# ONA_SensorMoteV1.net
KiCad netlist of a schematic drawn in EAGLE
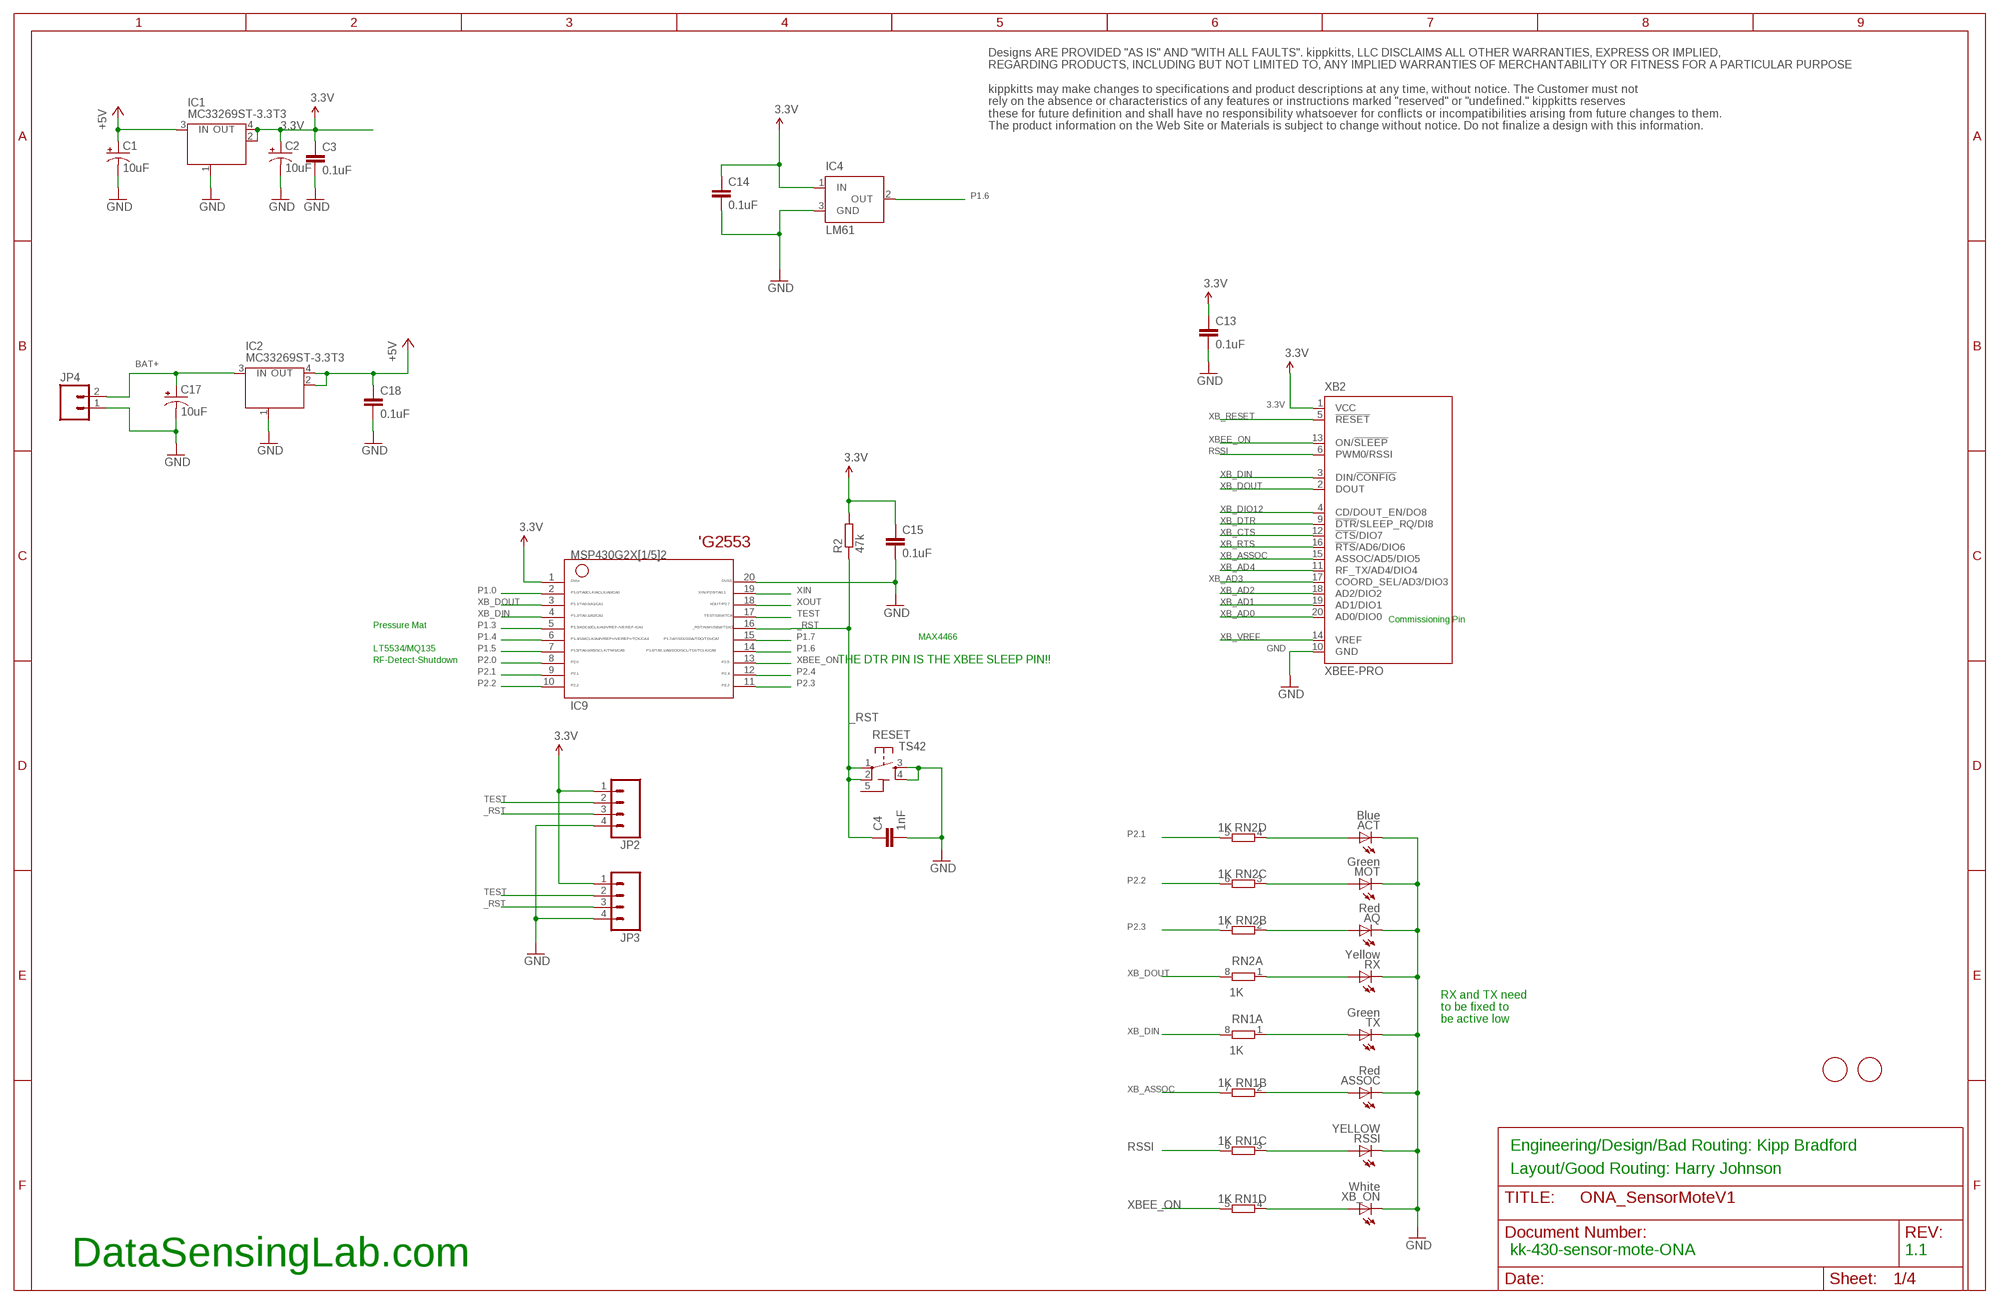
[diagram p0: schematic, sheet 1]
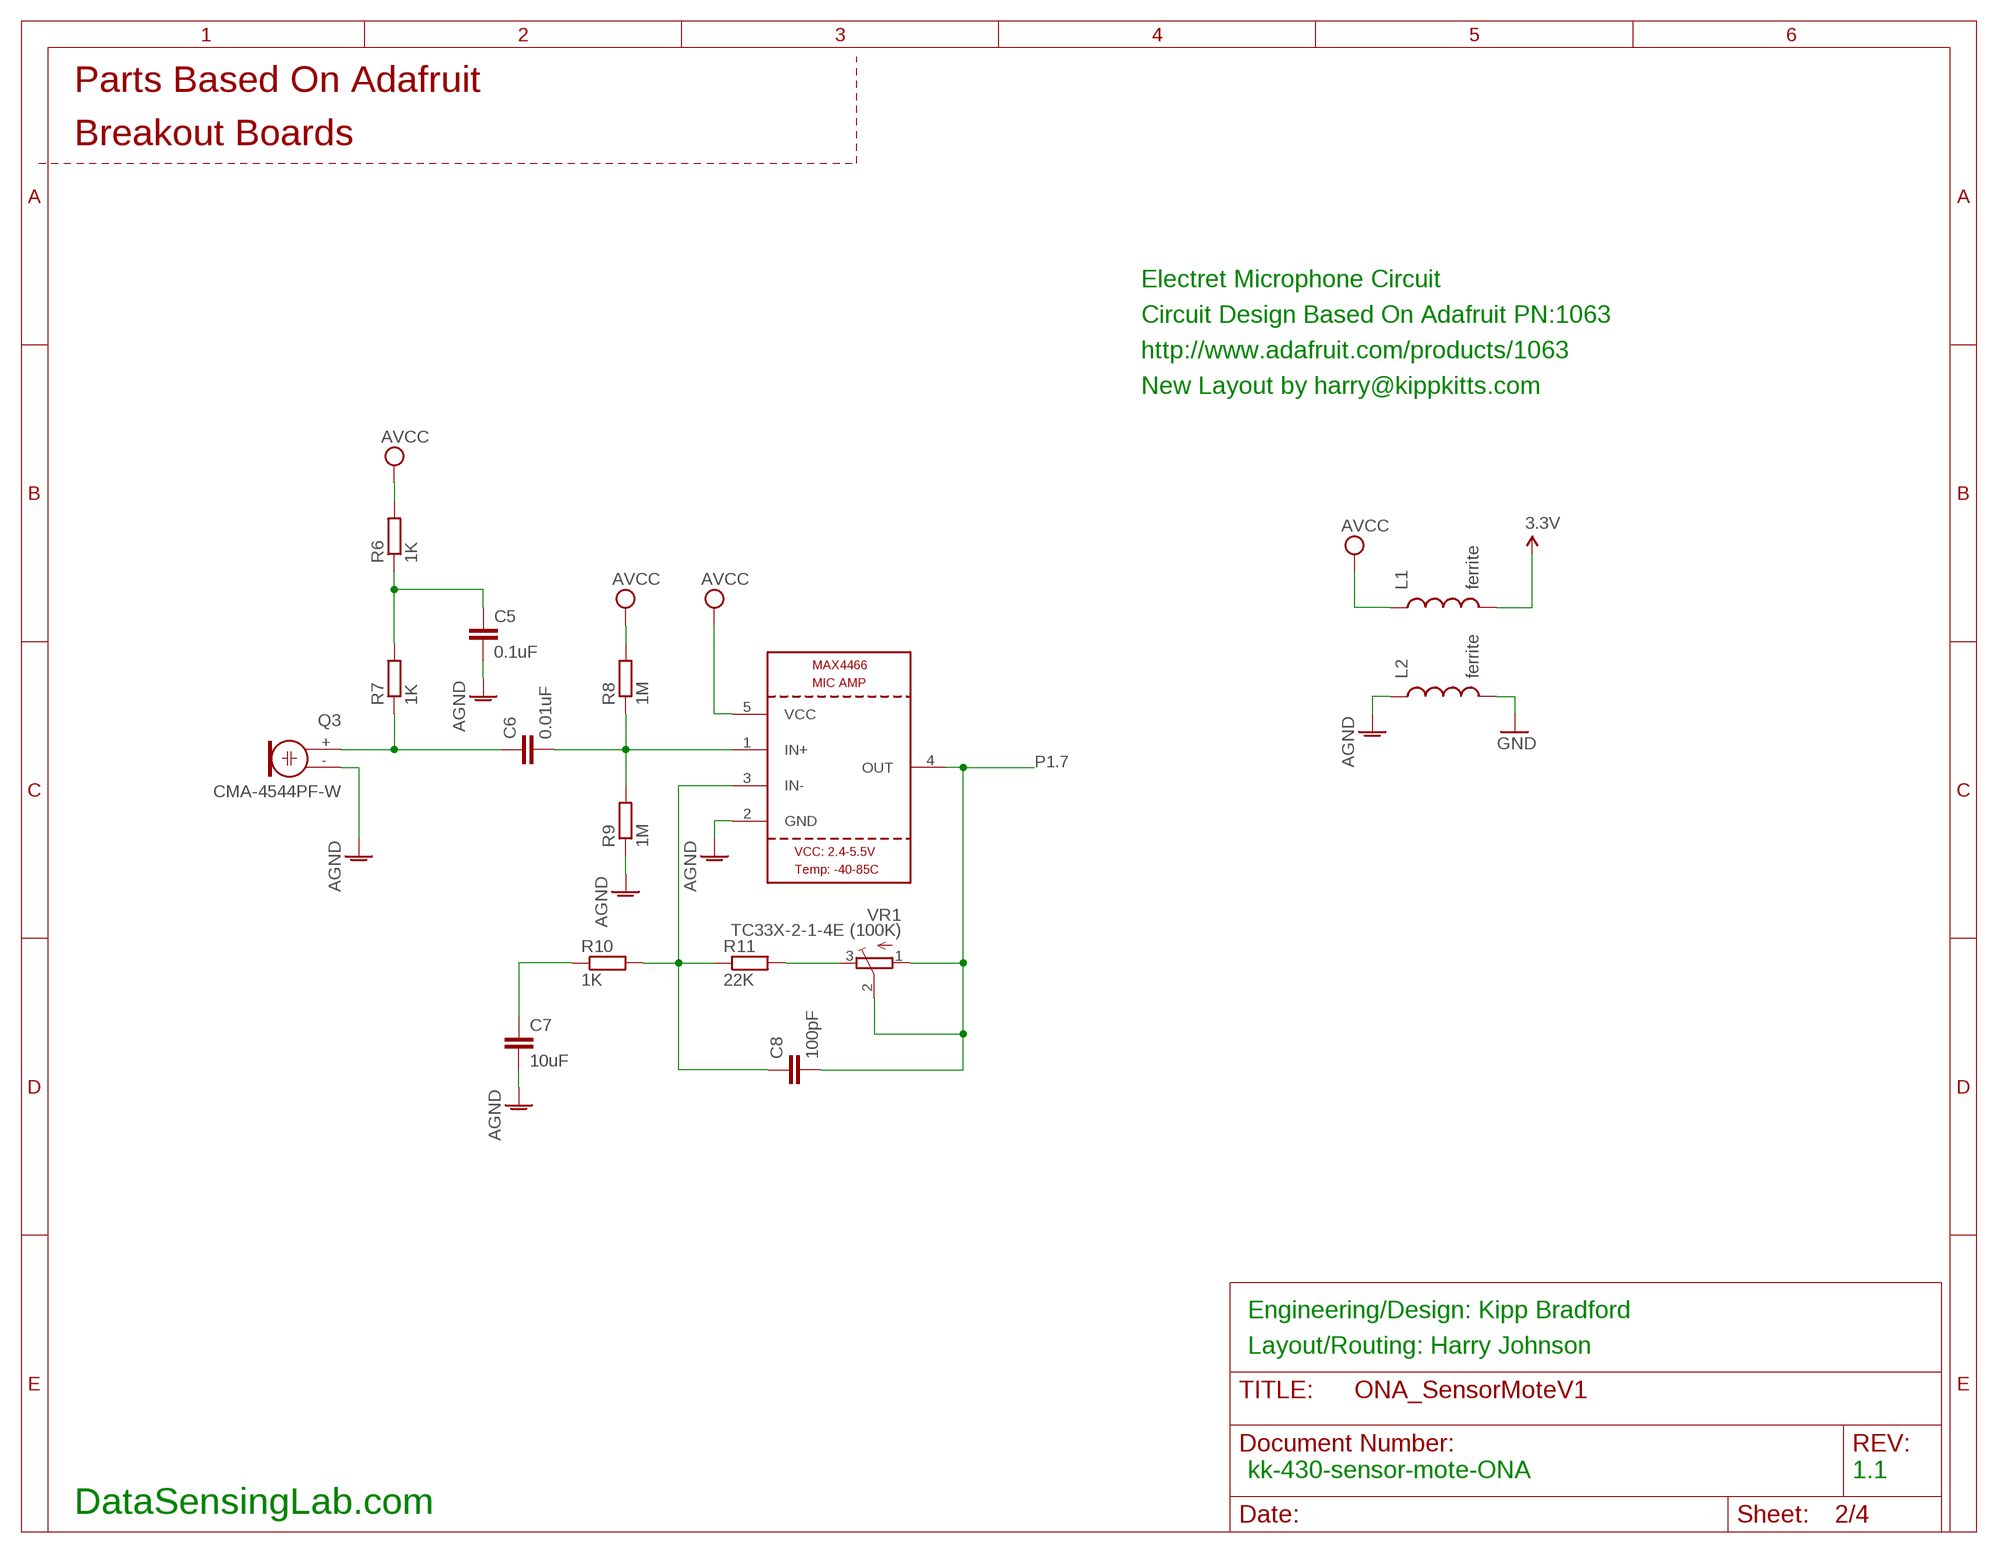
[diagram p1: schematic, sheet 2]
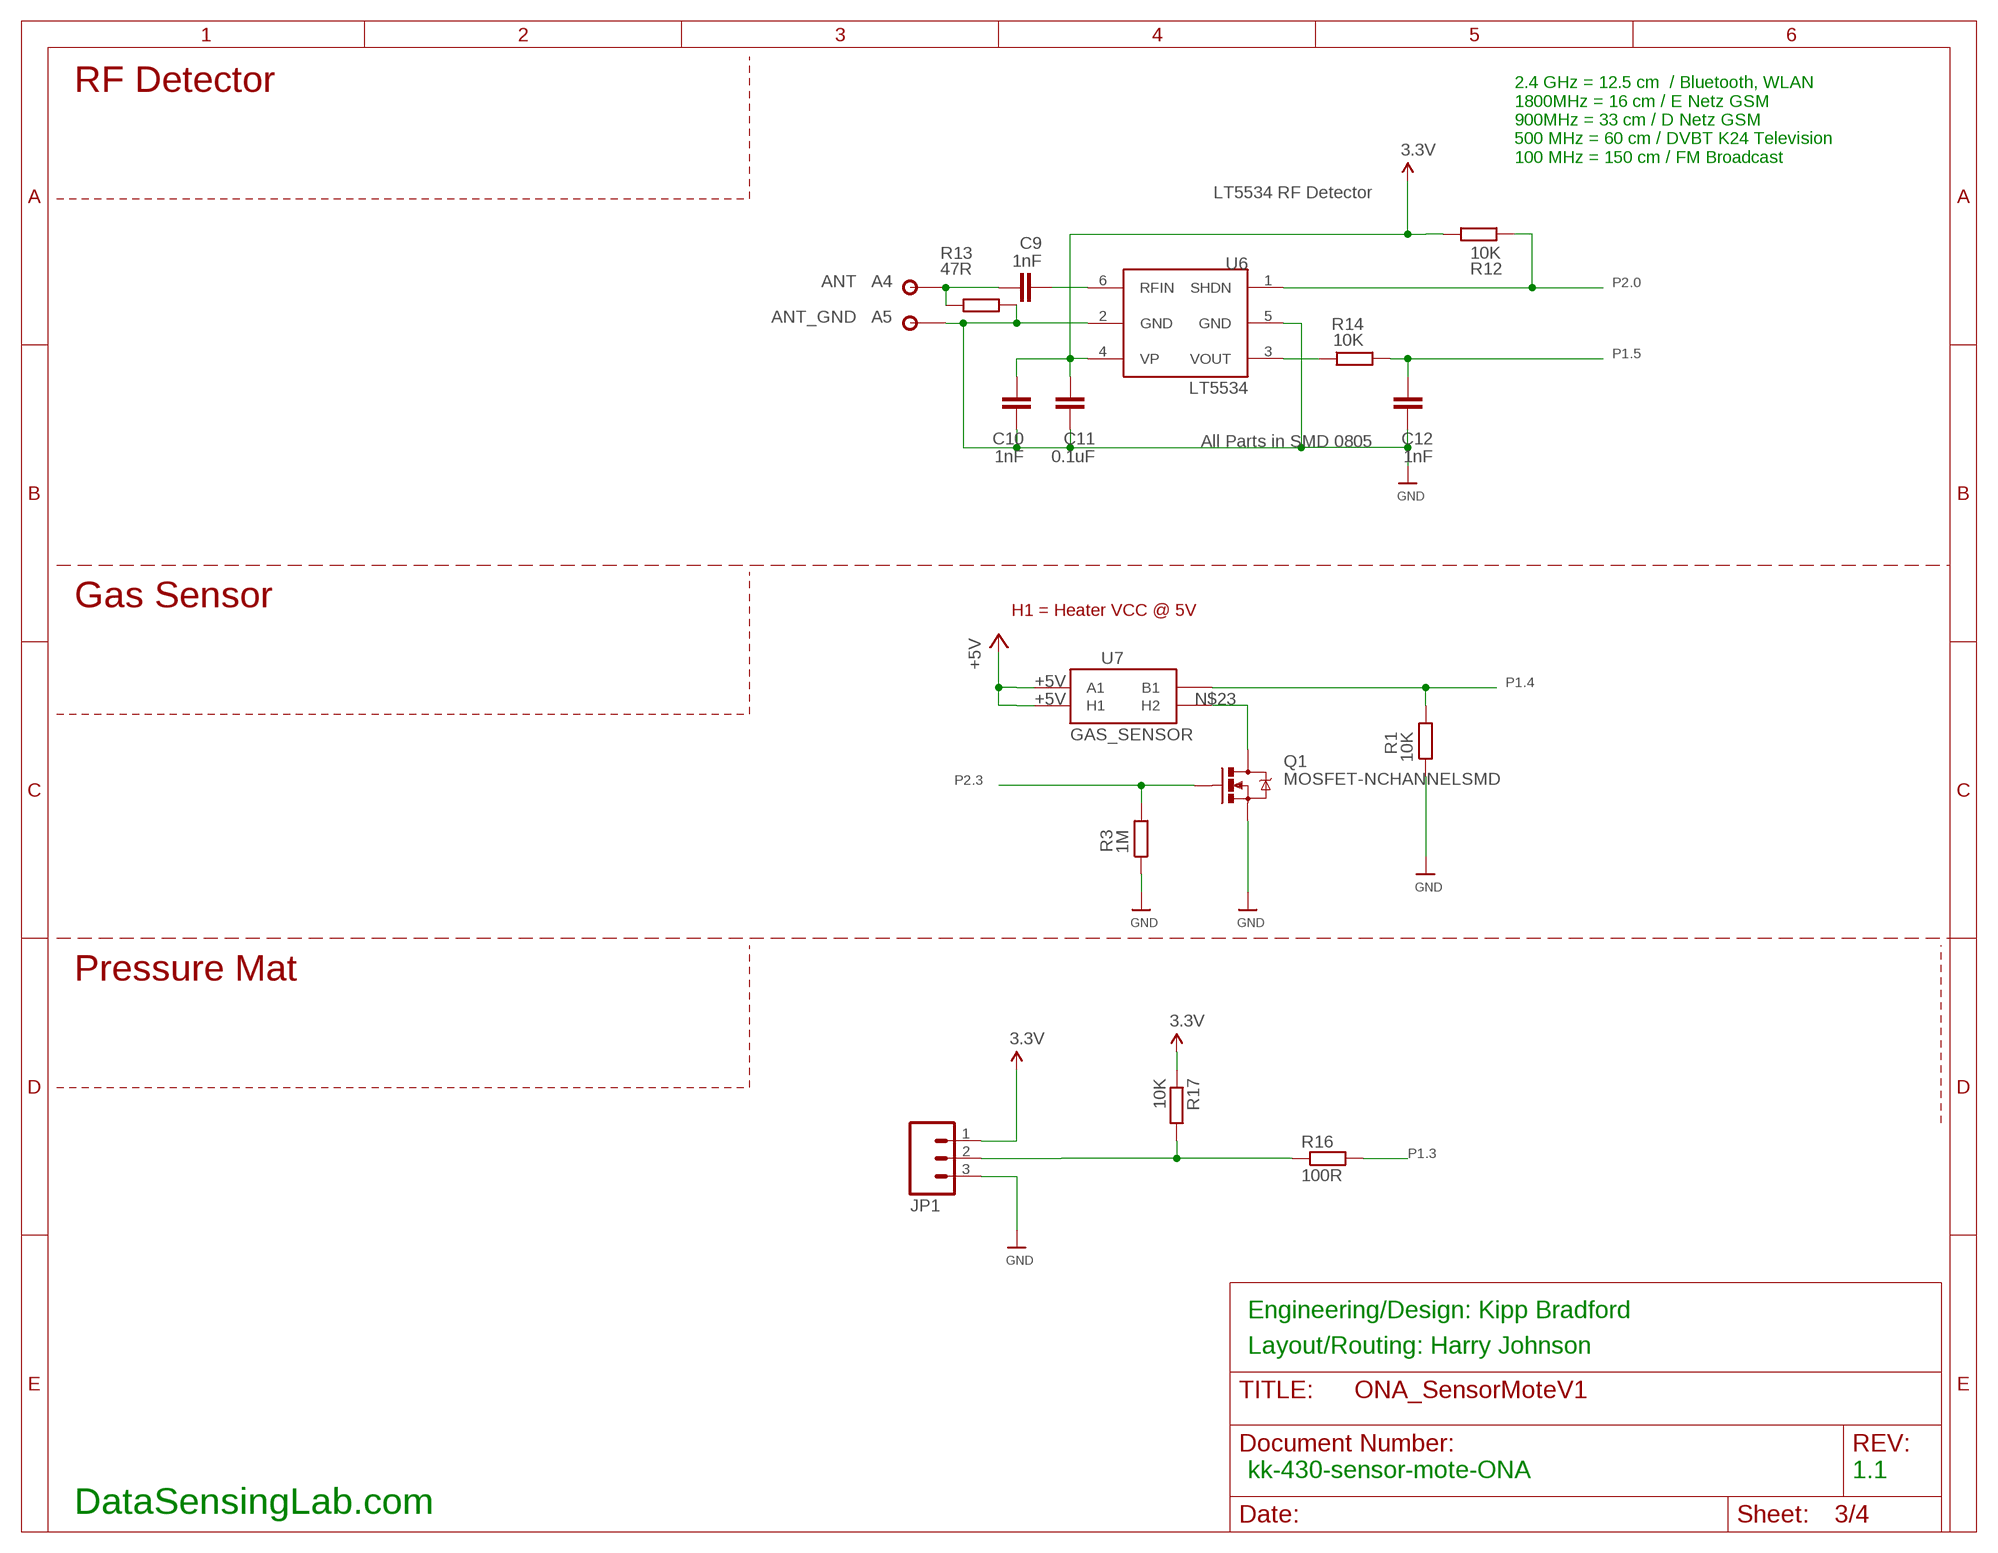
[diagram p2: schematic, sheet 3]
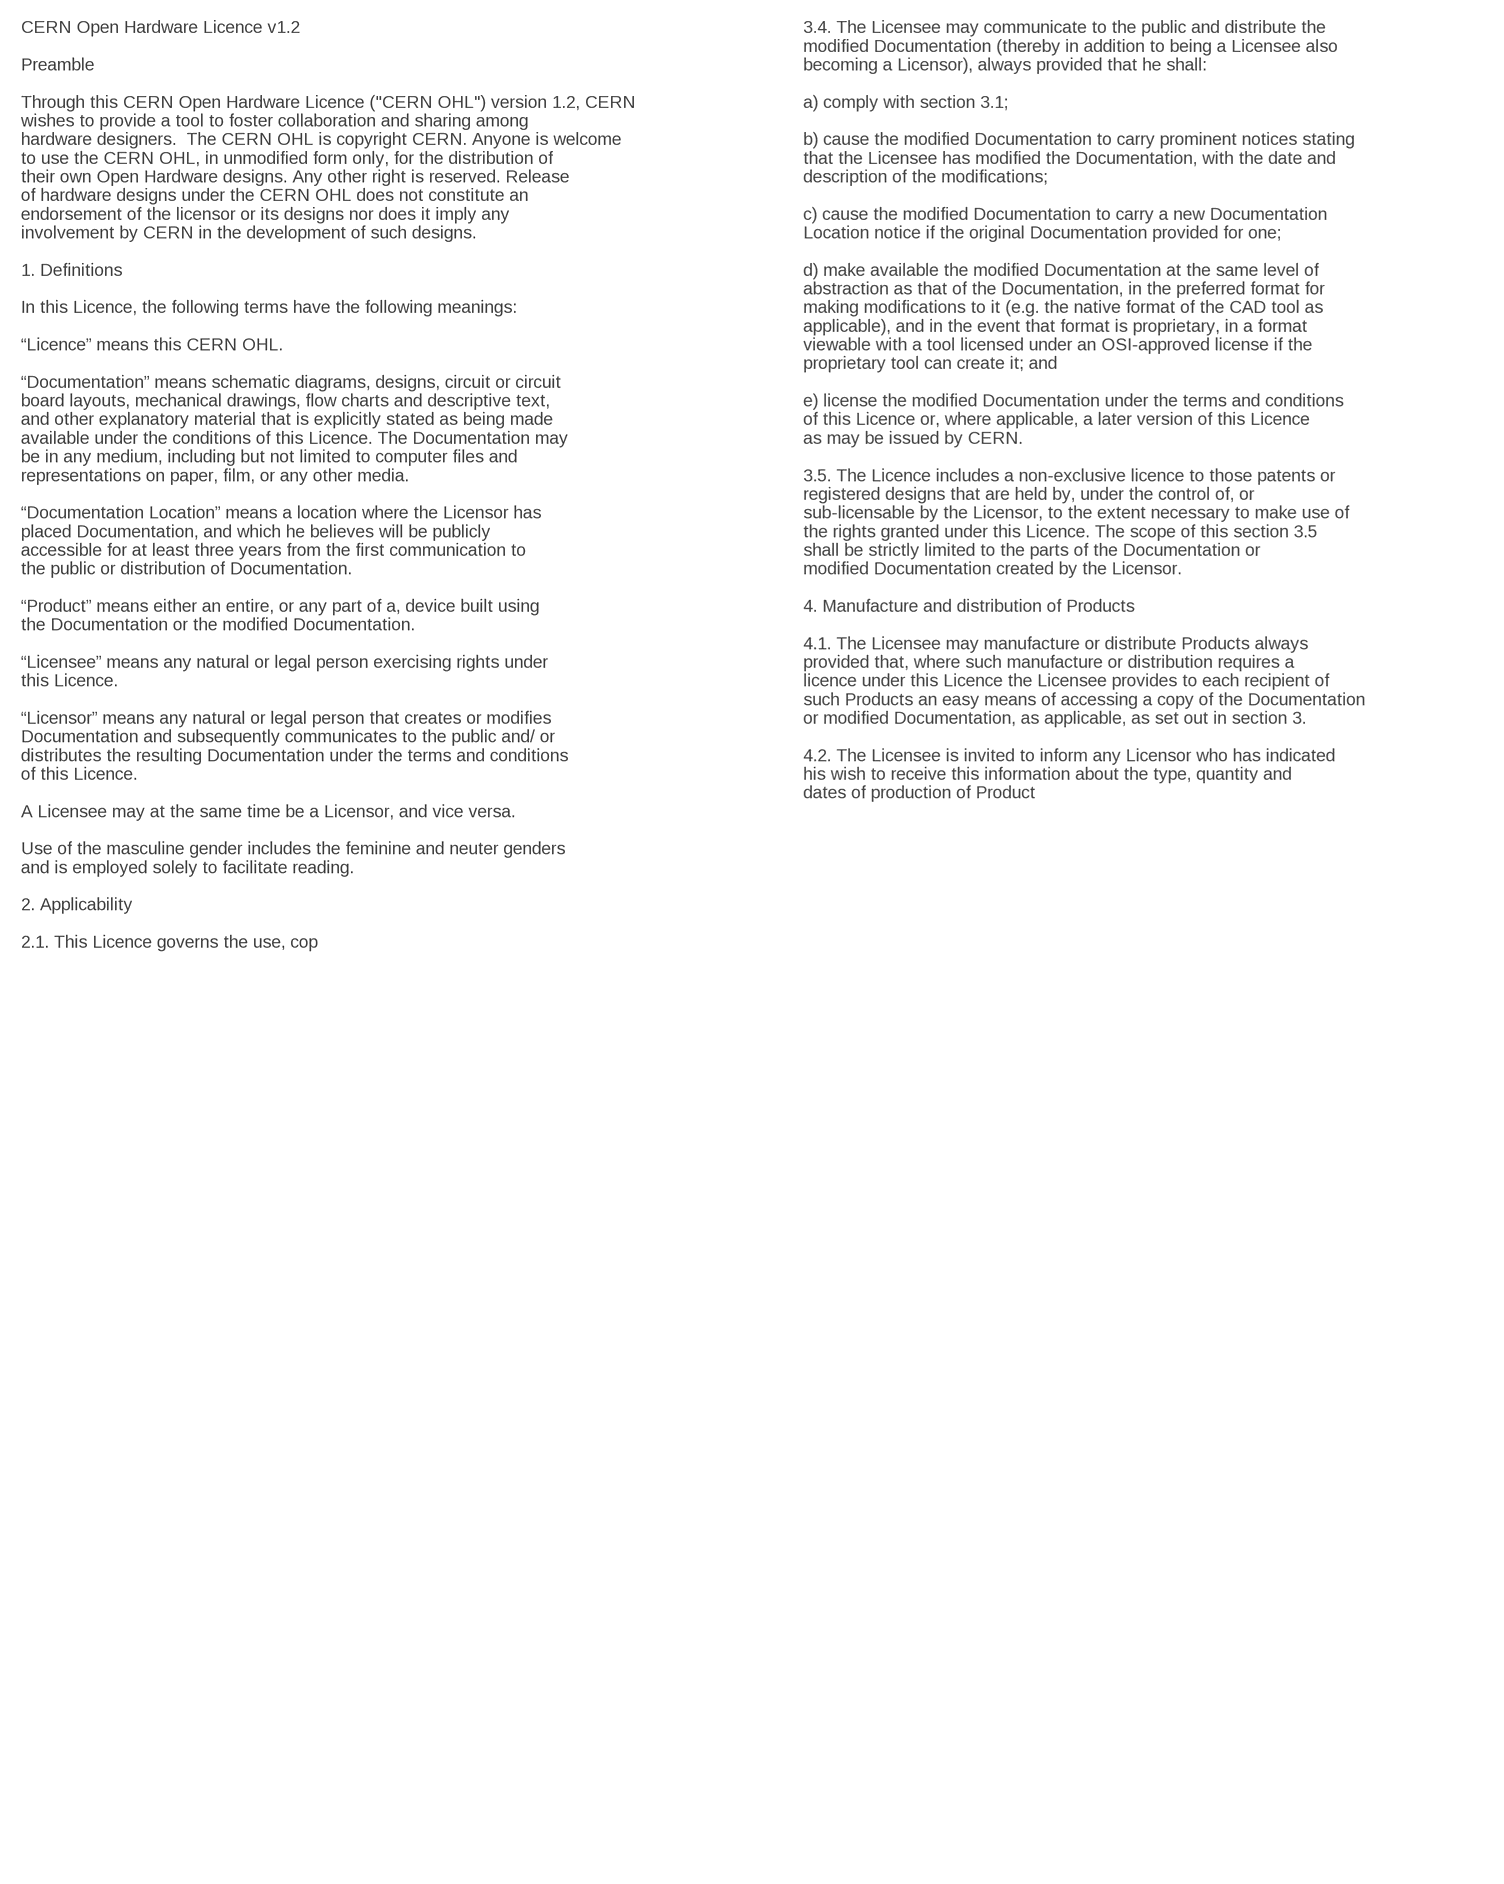
[diagram p3: schematic, sheet 4]

(export (version "E")
  (design (tool "Eeschema 10.0.6"))
  (components
    (comp (ref "A1")
      (value "FIDUCIALMOUNT")
      (footprint "eagle-import:FIDUCIA-MOUNT")
      (libsource (lib "eagle-import") (part "FIDUCIALMOUNT"))
    )
    (comp (ref "A2")
      (value "FIDUCIALMOUNT")
      (footprint "eagle-import:FIDUCIA-MOUNT")
      (libsource (lib "eagle-import") (part "FIDUCIALMOUNT"))
    )
    (comp (ref "ACT")
      (value "Blue")
      (footprint "eagle-import:CHIP-LED0805")
      (libsource (lib "eagle-import") (part "LEDCHIP-LED0805"))
    )
    (comp (ref "AQ")
      (value "Red")
      (footprint "eagle-import:CHIP-LED0805")
      (libsource (lib "eagle-import") (part "LEDCHIP-LED0805"))
    )
    (comp (ref "ASSOC")
      (value "Red")
      (footprint "eagle-import:CHIP-LED0805")
      (libsource (lib "eagle-import") (part "LEDCHIP-LED0805"))
    )
    (comp (ref "C1")
      (value "10uF")
      (footprint "eagle-import:EIA3216")
      (libsource (lib "eagle-import") (part "CAP_POL1206"))
    )
    (comp (ref "C2")
      (value "10uF")
      (footprint "eagle-import:EIA3216")
      (libsource (lib "eagle-import") (part "CAP_POL1206"))
    )
    (comp (ref "C3")
      (value "0.1uF")
      (footprint "eagle-import:C0805K")
      (libsource (lib "eagle-import") (part "C-EUC0805K"))
    )
    (comp (ref "C4")
      (value "1nF")
      (footprint "eagle-import:C0805K")
      (libsource (lib "eagle-import") (part "C-EUC0805K"))
    )
    (comp (ref "C13")
      (value "0.1uF")
      (footprint "eagle-import:C0805K")
      (libsource (lib "eagle-import") (part "C-EUC0805K"))
    )
    (comp (ref "C14")
      (value "0.1uF")
      (footprint "eagle-import:C0805K")
      (libsource (lib "eagle-import") (part "C-EUC0805K"))
    )
    (comp (ref "C15")
      (value "0.1uF")
      (footprint "eagle-import:C0805K")
      (libsource (lib "eagle-import") (part "C-EUC0805K"))
    )
    (comp (ref "C17")
      (value "10uF")
      (footprint "eagle-import:EIA3216")
      (libsource (lib "eagle-import") (part "CAP_POL1206"))
    )
    (comp (ref "C18")
      (value "0.1uF")
      (footprint "eagle-import:C0805K")
      (libsource (lib "eagle-import") (part "C-EUC0805K"))
    )
    (comp (ref "DISCLAIMER1")
      (value "DISCLAIMERV1")
      (footprint "eagle-import:DISCLAIMER")
      (libsource (lib "eagle-import") (part "DISCLAIMERV1"))
    )
    (comp (ref "IC1")
      (value "MC33269ST-3.3T3")
      (footprint "eagle-import:SOT223")
      (libsource (lib "eagle-import") (part "MC33269ST-3.3T3"))
    )
    (comp (ref "IC2")
      (value "MC33269ST-3.3T3")
      (footprint "eagle-import:SOT223")
      (libsource (lib "eagle-import") (part "MC33269ST-3.3T3"))
    )
    (comp (ref "IC4")
      (value "LM61")
      (footprint "eagle-import:SOT23")
      (fields (field (name "MF") "MAXIM") (field (name "MPN") "MAX6520EUR-T"))
      (libsource (lib "eagle-import") (part "MAX6520"))
    )
    (comp (ref "IC9")
      (value "G2X[1/5]2---PW20")
      (footprint "eagle-import:PW20")
      (libsource (lib "eagle-import") (part "G2X[1/5]2---PW20"))
    )
    (comp (ref "JP2")
      (value "M04SMD")
      (footprint "eagle-import:1X04-SMD")
      (libsource (lib "eagle-import") (part "M04SMD"))
    )
    (comp (ref "JP3")
      (value "M04PTH")
      (footprint "eagle-import:1X04")
      (libsource (lib "eagle-import") (part "M04PTH"))
    )
    (comp (ref "JP4")
      (value "M02")
      (footprint "eagle-import:1X02_LONGPADS")
      (libsource (lib "eagle-import") (part "M02"))
    )
    (comp (ref "MOT")
      (value "Green")
      (footprint "eagle-import:CHIP-LED0805")
      (libsource (lib "eagle-import") (part "LEDCHIP-LED0805"))
    )
    (comp (ref "R2")
      (value "47k")
      (footprint "eagle-import:R0805")
      (libsource (lib "eagle-import") (part "resistor_R-EU_R0805"))
    )
    (comp (ref "RESET")
      (value "TS42")
      (footprint "eagle-import:TS42")
      (libsource (lib "eagle-import") (part "TS42"))
    )
    (comp (ref "RN1")
      (value "1K")
      (footprint "eagle-import:CAY16")
      (libsource (lib "eagle-import") (part "4R-NCAY16"))
    )
    (comp (ref "RN2")
      (value "1K")
      (footprint "eagle-import:CAY16")
      (fields (field (name "OC_FARNELL") "unknown") (field (name "OC_NEWARK") "unknown"))
      (libsource (lib "eagle-import") (part "4R-NCAY16"))
    )
    (comp (ref "RSSI")
      (value "YELLOW")
      (footprint "eagle-import:CHIP-LED0805")
      (libsource (lib "eagle-import") (part "LEDCHIP-LED0805"))
    )
    (comp (ref "RX")
      (value "Yellow")
      (footprint "eagle-import:CHIP-LED0805")
      (libsource (lib "eagle-import") (part "LEDCHIP-LED0805"))
    )
    (comp (ref "TX")
      (value "Green")
      (footprint "eagle-import:CHIP-LED0805")
      (libsource (lib "eagle-import") (part "LEDCHIP-LED0805"))
    )
    (comp (ref "XB2")
      (value "XBEE-PRO")
      (footprint "eagle-import:XBEE-PRO")
      (fields (field (name "MPN") "XBP24-AWI-001"))
      (libsource (lib "eagle-import") (part "XBEE-PRO"))
    )
    (comp (ref "XB_ON")
      (value "White")
      (footprint "eagle-import:CHIP-LED0805")
      (libsource (lib "eagle-import") (part "LEDCHIP-LED0805"))
    )
    (comp (ref "C5")
      (value "0.1uF")
      (footprint "eagle-import:C0805K")
      (libsource (lib "eagle-import") (part "C-EUC0805K"))
    )
    (comp (ref "C6")
      (value "0.01uF")
      (footprint "eagle-import:C0805K")
      (libsource (lib "eagle-import") (part "C-EUC0805K"))
    )
    (comp (ref "C7")
      (value "10uF")
      (footprint "eagle-import:C0805K")
      (libsource (lib "eagle-import") (part "C-EUC0805K"))
    )
    (comp (ref "C8")
      (value "100pF")
      (footprint "eagle-import:C0805K")
      (libsource (lib "eagle-import") (part "C-EUC0805K"))
    )
    (comp (ref "L1")
      (value "ferrite")
      (footprint "eagle-import:0603")
      (libsource (lib "eagle-import") (part "INDUCTOR0603"))
    )
    (comp (ref "L2")
      (value "ferrite")
      (footprint "eagle-import:0603")
      (libsource (lib "eagle-import") (part "INDUCTOR0603"))
    )
    (comp (ref "Q3")
      (value "CMA-4544PF-W")
      (footprint "eagle-import:9.7ELECTRET")
      (libsource (lib "eagle-import") (part "ELECTRET"))
    )
    (comp (ref "R6")
      (value "1K")
      (footprint "eagle-import:R0805")
      (libsource (lib "eagle-import") (part "resistor_R-EU_R0805"))
    )
    (comp (ref "R7")
      (value "1K")
      (footprint "eagle-import:R0805")
      (libsource (lib "eagle-import") (part "resistor_R-EU_R0805"))
    )
    (comp (ref "R8")
      (value "1M")
      (footprint "eagle-import:R0805")
      (libsource (lib "eagle-import") (part "resistor_R-EU_R0805"))
    )
    (comp (ref "R9")
      (value "1M")
      (footprint "eagle-import:R0805")
      (libsource (lib "eagle-import") (part "resistor_R-EU_R0805"))
    )
    (comp (ref "R10")
      (value "1K")
      (footprint "eagle-import:R0805")
      (libsource (lib "eagle-import") (part "resistor_R-EU_R0805"))
    )
    (comp (ref "R11")
      (value "22K")
      (footprint "eagle-import:R0805")
      (libsource (lib "eagle-import") (part "resistor_R-EU_R0805"))
    )
    (comp (ref "U5")
      (value "MAX4466SC70")
      (footprint "eagle-import:SC70-5L")
      (libsource (lib "eagle-import") (part "MAX4466SC70"))
    )
    (comp (ref "VR1")
      (value "TC33X-2-1-4E (100K)")
      (footprint "eagle-import:TC33X")
      (libsource (lib "eagle-import") (part "TRIMPOTTC33X"))
    )
    (comp (ref "A4")
      (value "ANT")
      (footprint "eagle-import:PAD146")
      (libsource (lib "eagle-import") (part "PAD1,46MM"))
    )
    (comp (ref "A5")
      (value "ANT_GND")
      (footprint "eagle-import:PAD146")
      (libsource (lib "eagle-import") (part "PAD1,46MM"))
    )
    (comp (ref "C9")
      (value "1nF")
      (footprint "eagle-import:C0805K")
      (libsource (lib "eagle-import") (part "C-EUC0805K"))
    )
    (comp (ref "C10")
      (value "1nF")
      (footprint "eagle-import:C0805K")
      (libsource (lib "eagle-import") (part "C-EUC0805K"))
    )
    (comp (ref "C11")
      (value "0.1uF")
      (footprint "eagle-import:C0805K")
      (libsource (lib "eagle-import") (part "C-EUC0805K"))
    )
    (comp (ref "C12")
      (value "1nF")
      (footprint "eagle-import:C0805K")
      (libsource (lib "eagle-import") (part "C-EUC0805K"))
    )
    (comp (ref "JP1")
      (value "M03LOCK")
      (footprint "eagle-import:1X03_LOCK")
      (libsource (lib "eagle-import") (part "M03LOCK"))
    )
    (comp (ref "Q1")
      (value "MOSFET-NCHANNELSMD")
      (footprint "eagle-import:SOT23-3")
      (libsource (lib "eagle-import") (part "MOSFET-NCHANNELSMD"))
    )
    (comp (ref "R1")
      (value "10K")
      (footprint "eagle-import:R0805")
      (libsource (lib "eagle-import") (part "R-EU_R0805"))
    )
    (comp (ref "R3")
      (value "1M")
      (footprint "eagle-import:R0805")
      (libsource (lib "eagle-import") (part "R-EU_R0805"))
    )
    (comp (ref "R12")
      (value "10K")
      (footprint "eagle-import:R0805")
      (libsource (lib "eagle-import") (part "R-EU_R0805"))
    )
    (comp (ref "R13")
      (value "47R")
      (footprint "eagle-import:R0805")
      (libsource (lib "eagle-import") (part "R-EU_R0805"))
    )
    (comp (ref "R14")
      (value "10K")
      (footprint "eagle-import:R0805")
      (libsource (lib "eagle-import") (part "R-EU_R0805"))
    )
    (comp (ref "R16")
      (value "100R")
      (footprint "eagle-import:R0805")
      (libsource (lib "eagle-import") (part "R-EU_R0805"))
    )
    (comp (ref "R17")
      (value "10K")
      (footprint "eagle-import:R0805")
      (libsource (lib "eagle-import") (part "R-EU_R0805"))
    )
    (comp (ref "U6")
      (value "LT5534")
      (footprint "eagle-import:SC70")
      (libsource (lib "eagle-import") (part "LTC55"))
    )
    (comp (ref "U7")
      (value "GAS_SENSOR")
      (footprint "eagle-import:MQ-3")
      (libsource (lib "eagle-import") (part "GAS_SENSOR"))
    )
  )
  (nets
    (net (code "1") (name "+5V") (class "Default")
      (node (ref "C1") (pin "A") (pinfunction "+_A") (pintype "passive"))
      (node (ref "C18") (pin "1") (pinfunction "1_1") (pintype "passive"))
      (node (ref "IC1") (pin "3") (pinfunction "IN_3") (pintype "input"))
      (node (ref "IC2") (pin "2") (pinfunction "OUT_2") (pintype "passive"))
      (node (ref "IC2") (pin "4") (pinfunction "OUT_4") (pintype "passive"))
      (node (ref "U7") (pin "A1") (pinfunction "A1_A1") (pintype "bidirectional"))
      (node (ref "U7") (pin "HA") (pinfunction "H1_HA") (pintype "bidirectional"))
    )
    (net (code "2") (name "3.3V") (class "Default")
      (node (ref "C10") (pin "2") (pinfunction "2_2") (pintype "passive"))
      (node (ref "C11") (pin "2") (pinfunction "2_2") (pintype "passive"))
      (node (ref "C13") (pin "1") (pinfunction "1_1") (pintype "passive"))
      (node (ref "C14") (pin "1") (pinfunction "1_1") (pintype "passive"))
      (node (ref "C15") (pin "1") (pinfunction "1_1") (pintype "passive"))
      (node (ref "C2") (pin "A") (pinfunction "+_A") (pintype "passive"))
      (node (ref "C3") (pin "1") (pinfunction "1_1") (pintype "passive"))
      (node (ref "IC1") (pin "2") (pinfunction "OUT_2") (pintype "passive"))
      (node (ref "IC1") (pin "4") (pinfunction "OUT_4") (pintype "passive"))
      (node (ref "IC4") (pin "1") (pinfunction "IN_1") (pintype "input"))
      (node (ref "IC9") (pin "1") (pinfunction "1_1") (pintype "bidirectional"))
      (node (ref "JP1") (pin "1") (pinfunction "1_1") (pintype "passive"))
      (node (ref "JP2") (pin "1") (pinfunction "1_1") (pintype "passive"))
      (node (ref "JP3") (pin "1") (pinfunction "1_1") (pintype "passive"))
      (node (ref "L1") (pin "2") (pinfunction "2_2") (pintype "passive"))
      (node (ref "R12") (pin "2") (pinfunction "2_2") (pintype "passive"))
      (node (ref "R17") (pin "1") (pinfunction "1_1") (pintype "passive"))
      (node (ref "R2") (pin "2") (pinfunction "2_2") (pintype "passive"))
      (node (ref "U6") (pin "4") (pinfunction "VP_4") (pintype "bidirectional"))
      (node (ref "XB2") (pin "1") (pinfunction "VCC_1") (pintype "power_in"))
    )
    (net (code "3") (name "5-GND") (class "Default")
      (node (ref "RESET") (pin "5") (pinfunction "5-GND_5") (pintype "power_in"))
    )
    (net (code "4") (name "AGND") (class "Default")
      (node (ref "C5") (pin "2") (pinfunction "2_2") (pintype "passive"))
      (node (ref "C7") (pin "2") (pinfunction "2_2") (pintype "passive"))
      (node (ref "L2") (pin "1") (pinfunction "1_1") (pintype "passive"))
      (node (ref "Q3") (pin "-") (pinfunction "1_-") (pintype "passive"))
      (node (ref "R9") (pin "1") (pinfunction "1_1") (pintype "passive"))
      (node (ref "U5") (pin "2") (pinfunction "GND_2") (pintype "power_in"))
    )
    (net (code "5") (name "BAT+") (class "Default")
      (node (ref "C17") (pin "A") (pinfunction "+_A") (pintype "passive"))
      (node (ref "IC2") (pin "3") (pinfunction "IN_3") (pintype "input"))
      (node (ref "JP4") (pin "2") (pinfunction "2_2") (pintype "passive"))
    )
    (net (code "6") (name "GND") (class "Default")
      (node (ref "A5") (pin "1") (pinfunction "1_1") (pintype "passive"))
      (node (ref "ACT") (pin "C") (pinfunction "C_C") (pintype "passive"))
      (node (ref "AQ") (pin "C") (pinfunction "C_C") (pintype "passive"))
      (node (ref "ASSOC") (pin "C") (pinfunction "C_C") (pintype "passive"))
      (node (ref "C1") (pin "C") (pinfunction "-_C") (pintype "passive"))
      (node (ref "C10") (pin "1") (pinfunction "1_1") (pintype "passive"))
      (node (ref "C11") (pin "1") (pinfunction "1_1") (pintype "passive"))
      (node (ref "C12") (pin "1") (pinfunction "1_1") (pintype "passive"))
      (node (ref "C13") (pin "2") (pinfunction "2_2") (pintype "passive"))
      (node (ref "C14") (pin "2") (pinfunction "2_2") (pintype "passive"))
      (node (ref "C15") (pin "2") (pinfunction "2_2") (pintype "passive"))
      (node (ref "C17") (pin "C") (pinfunction "-_C") (pintype "passive"))
      (node (ref "C18") (pin "2") (pinfunction "2_2") (pintype "passive"))
      (node (ref "C2") (pin "C") (pinfunction "-_C") (pintype "passive"))
      (node (ref "C3") (pin "2") (pinfunction "2_2") (pintype "passive"))
      (node (ref "C4") (pin "2") (pinfunction "2_2") (pintype "passive"))
      (node (ref "IC1") (pin "1") (pinfunction "GND/ADJ_1") (pintype "input"))
      (node (ref "IC2") (pin "1") (pinfunction "GND/ADJ_1") (pintype "input"))
      (node (ref "IC4") (pin "3") (pinfunction "GND_3") (pintype "power_in"))
      (node (ref "IC9") (pin "20") (pinfunction "20_20") (pintype "bidirectional"))
      (node (ref "JP1") (pin "3") (pinfunction "3_3") (pintype "passive"))
      (node (ref "JP2") (pin "4") (pinfunction "4_4") (pintype "passive"))
      (node (ref "JP3") (pin "4") (pinfunction "4_4") (pintype "passive"))
      (node (ref "JP4") (pin "1") (pinfunction "1_1") (pintype "passive"))
      (node (ref "L2") (pin "2") (pinfunction "2_2") (pintype "passive"))
      (node (ref "MOT") (pin "C") (pinfunction "C_C") (pintype "passive"))
      (node (ref "Q1") (pin "2") (pinfunction "S_2") (pintype "passive"))
      (node (ref "R1") (pin "1") (pinfunction "1_1") (pintype "passive"))
      (node (ref "R13") (pin "2") (pinfunction "2_2") (pintype "passive"))
      (node (ref "R3") (pin "1") (pinfunction "1_1") (pintype "passive"))
      (node (ref "RESET") (pin "3") (pinfunction "3_3") (pintype "passive"))
      (node (ref "RESET") (pin "4") (pinfunction "4_4") (pintype "passive"))
      (node (ref "RSSI") (pin "C") (pinfunction "C_C") (pintype "passive"))
      (node (ref "RX") (pin "C") (pinfunction "C_C") (pintype "passive"))
      (node (ref "TX") (pin "C") (pinfunction "C_C") (pintype "passive"))
      (node (ref "U6") (pin "2") (pinfunction "GND_2") (pintype "power_in"))
      (node (ref "U6") (pin "5") (pinfunction "GND_5") (pintype "power_in"))
      (node (ref "XB2") (pin "10") (pinfunction "GND_10") (pintype "power_in"))
      (node (ref "XB_ON") (pin "C") (pinfunction "C_C") (pintype "passive"))
    )
    (net (code "7") (name "N$23") (class "Default")
      (node (ref "Q1") (pin "3") (pinfunction "D_3") (pintype "passive"))
      (node (ref "U7") (pin "HB") (pinfunction "H2_HB") (pintype "bidirectional"))
    )
    (net (code "8") (name "Net-(A4-Pad1)") (class "Default")
      (node (ref "A4") (pin "1") (pinfunction "1_1") (pintype "passive"))
      (node (ref "C9") (pin "2") (pinfunction "2_2") (pintype "passive"))
      (node (ref "R13") (pin "1") (pinfunction "1_1") (pintype "passive"))
    )
    (net (code "9") (name "Net-(C5-Pad1)") (class "Default")
      (node (ref "C5") (pin "1") (pinfunction "1_1") (pintype "passive"))
      (node (ref "R6") (pin "1") (pinfunction "1_1") (pintype "passive"))
      (node (ref "R7") (pin "2") (pinfunction "2_2") (pintype "passive"))
    )
    (net (code "10") (name "Net-(C7-Pad1)") (class "Default")
      (node (ref "C7") (pin "1") (pinfunction "1_1") (pintype "passive"))
      (node (ref "R10") (pin "1") (pinfunction "1_1") (pintype "passive"))
    )
    (net (code "11") (name "Net-(JP1-Pad2)") (class "Default")
      (node (ref "JP1") (pin "2") (pinfunction "2_2") (pintype "passive"))
      (node (ref "R16") (pin "1") (pinfunction "1_1") (pintype "passive"))
      (node (ref "R17") (pin "2") (pinfunction "2_2") (pintype "passive"))
    )
    (net (code "12") (name "Net-(Q3-2)") (class "Default")
      (node (ref "C6") (pin "1") (pinfunction "1_1") (pintype "passive"))
      (node (ref "Q3") (pin "+") (pinfunction "2_+") (pintype "passive"))
      (node (ref "R7") (pin "1") (pinfunction "1_1") (pintype "passive"))
    )
    (net (code "13") (name "Net-(RN1-Pad1)") (class "Default")
      (node (ref "RN1") (pin "1") (pinfunction "1_1") (pintype "passive"))
      (node (ref "TX") (pin "A") (pinfunction "A_A") (pintype "passive"))
    )
    (net (code "14") (name "Net-(RN1B-1)") (class "Default")
      (node (ref "ASSOC") (pin "A") (pinfunction "A_A") (pintype "passive"))
      (node (ref "RN1") (pin "2") (pinfunction "1_2") (pintype "passive"))
    )
    (net (code "15") (name "Net-(RN1C-1)") (class "Default")
      (node (ref "RN1") (pin "3") (pinfunction "1_3") (pintype "passive"))
      (node (ref "RSSI") (pin "A") (pinfunction "A_A") (pintype "passive"))
    )
    (net (code "16") (name "Net-(RN1D-1)") (class "Default")
      (node (ref "RN1") (pin "4") (pinfunction "1_4") (pintype "passive"))
      (node (ref "XB_ON") (pin "A") (pinfunction "A_A") (pintype "passive"))
    )
    (net (code "17") (name "Net-(RN2-Pad1)") (class "Default")
      (node (ref "RN2") (pin "1") (pinfunction "1_1") (pintype "passive"))
      (node (ref "RX") (pin "A") (pinfunction "A_A") (pintype "passive"))
    )
    (net (code "18") (name "Net-(RN2B-1)") (class "Default")
      (node (ref "AQ") (pin "A") (pinfunction "A_A") (pintype "passive"))
      (node (ref "RN2") (pin "2") (pinfunction "1_2") (pintype "passive"))
    )
    (net (code "19") (name "Net-(RN2C-1)") (class "Default")
      (node (ref "MOT") (pin "A") (pinfunction "A_A") (pintype "passive"))
      (node (ref "RN2") (pin "3") (pinfunction "1_3") (pintype "passive"))
    )
    (net (code "20") (name "Net-(RN2D-1)") (class "Default")
      (node (ref "ACT") (pin "A") (pinfunction "A_A") (pintype "passive"))
      (node (ref "RN2") (pin "4") (pinfunction "1_4") (pintype "passive"))
    )
    (net (code "21") (name "Net-(U5-IN+)") (class "Default")
      (node (ref "C6") (pin "2") (pinfunction "2_2") (pintype "passive"))
      (node (ref "R8") (pin "1") (pinfunction "1_1") (pintype "passive"))
      (node (ref "R9") (pin "2") (pinfunction "2_2") (pintype "passive"))
      (node (ref "U5") (pin "1") (pinfunction "IN+_1") (pintype "input"))
    )
    (net (code "22") (name "Net-(U5-IN-)") (class "Default")
      (node (ref "C8") (pin "1") (pinfunction "1_1") (pintype "passive"))
      (node (ref "R10") (pin "2") (pinfunction "2_2") (pintype "passive"))
      (node (ref "R11") (pin "1") (pinfunction "1_1") (pintype "passive"))
      (node (ref "U5") (pin "3") (pinfunction "IN-_3") (pintype "input"))
    )
    (net (code "23") (name "Net-(U6-RFIN)") (class "Default")
      (node (ref "C9") (pin "1") (pinfunction "1_1") (pintype "passive"))
      (node (ref "U6") (pin "6") (pinfunction "RFIN_6") (pintype "bidirectional"))
    )
    (net (code "24") (name "Net-(U6-VOUT)") (class "Default")
      (node (ref "R14") (pin "1") (pinfunction "1_1") (pintype "passive"))
      (node (ref "U6") (pin "3") (pinfunction "VOUT_3") (pintype "bidirectional"))
    )
    (net (code "25") (name "Net-(VR1-E)") (class "Default")
      (node (ref "R11") (pin "2") (pinfunction "2_2") (pintype "passive"))
      (node (ref "VR1") (pin "3") (pinfunction "E_3") (pintype "passive"))
    )
    (net (code "26") (name "P1.0") (class "Default")
      (node (ref "IC9") (pin "2") (pinfunction "2_2") (pintype "bidirectional"))
    )
    (net (code "27") (name "P1.3") (class "Default")
      (node (ref "IC9") (pin "5") (pinfunction "5_5") (pintype "bidirectional"))
      (node (ref "R16") (pin "2") (pinfunction "2_2") (pintype "passive"))
    )
    (net (code "28") (name "P1.4") (class "Default")
      (node (ref "IC9") (pin "6") (pinfunction "6_6") (pintype "bidirectional"))
      (node (ref "R1") (pin "2") (pinfunction "2_2") (pintype "passive"))
      (node (ref "U7") (pin "B1") (pinfunction "B1_B1") (pintype "bidirectional"))
    )
    (net (code "29") (name "P1.5") (class "Default")
      (node (ref "C12") (pin "2") (pinfunction "2_2") (pintype "passive"))
      (node (ref "IC9") (pin "7") (pinfunction "7_7") (pintype "bidirectional"))
      (node (ref "R14") (pin "2") (pinfunction "2_2") (pintype "passive"))
    )
    (net (code "30") (name "P1.6") (class "Default")
      (node (ref "IC4") (pin "2") (pinfunction "OUT_2") (pintype "output"))
      (node (ref "IC9") (pin "14") (pinfunction "14_14") (pintype "bidirectional"))
    )
    (net (code "31") (name "P1.7") (class "Default")
      (node (ref "C8") (pin "2") (pinfunction "2_2") (pintype "passive"))
      (node (ref "IC9") (pin "15") (pinfunction "15_15") (pintype "bidirectional"))
      (node (ref "U5") (pin "4") (pinfunction "OUT_4") (pintype "output"))
      (node (ref "VR1") (pin "1") (pinfunction "A_1") (pintype "passive"))
      (node (ref "VR1") (pin "2") (pinfunction "S_2") (pintype "passive"))
    )
    (net (code "32") (name "P2.0") (class "Default")
      (node (ref "IC9") (pin "8") (pinfunction "8_8") (pintype "bidirectional"))
      (node (ref "R12") (pin "1") (pinfunction "1_1") (pintype "passive"))
      (node (ref "U6") (pin "1") (pinfunction "SHDN_1") (pintype "bidirectional"))
    )
    (net (code "33") (name "P2.1") (class "Default")
      (node (ref "IC9") (pin "9") (pinfunction "9_9") (pintype "bidirectional"))
      (node (ref "RN2") (pin "5") (pinfunction "2_5") (pintype "passive"))
    )
    (net (code "34") (name "P2.2") (class "Default")
      (node (ref "IC9") (pin "10") (pinfunction "10_10") (pintype "bidirectional"))
      (node (ref "RN2") (pin "6") (pinfunction "2_6") (pintype "passive"))
    )
    (net (code "35") (name "P2.3") (class "Default")
      (node (ref "IC9") (pin "11") (pinfunction "11_11") (pintype "bidirectional"))
      (node (ref "Q1") (pin "1") (pinfunction "G_1") (pintype "passive"))
      (node (ref "R3") (pin "2") (pinfunction "2_2") (pintype "passive"))
      (node (ref "RN2") (pin "7") (pinfunction "2_7") (pintype "passive"))
    )
    (net (code "36") (name "P2.4") (class "Default")
      (node (ref "IC9") (pin "12") (pinfunction "12_12") (pintype "bidirectional"))
    )
    (net (code "37") (name "RSSI") (class "Default")
      (node (ref "RN1") (pin "6") (pinfunction "2_6") (pintype "passive"))
      (node (ref "XB2") (pin "6") (pinfunction "PWM0/RSSI_6") (pintype "output"))
    )
    (net (code "38") (name "TEST") (class "Default")
      (node (ref "IC9") (pin "17") (pinfunction "17_17") (pintype "bidirectional"))
      (node (ref "JP2") (pin "2") (pinfunction "2_2") (pintype "passive"))
      (node (ref "JP3") (pin "2") (pinfunction "2_2") (pintype "passive"))
    )
    (net (code "39") (name "VCC") (class "Default")
      (node (ref "L1") (pin "1") (pinfunction "1_1") (pintype "passive"))
      (node (ref "R6") (pin "2") (pinfunction "2_2") (pintype "passive"))
      (node (ref "R8") (pin "2") (pinfunction "2_2") (pintype "passive"))
      (node (ref "U5") (pin "5") (pinfunction "VCC_5") (pintype "power_in"))
    )
    (net (code "40") (name "XBEE_ON") (class "Default")
      (node (ref "IC9") (pin "13") (pinfunction "13_13") (pintype "bidirectional"))
      (node (ref "RN1") (pin "5") (pinfunction "2_5") (pintype "passive"))
      (node (ref "XB2") (pin "13") (pinfunction "ON/~{SLEEP}_13") (pintype "output"))
    )
    (net (code "41") (name "XB_AD0") (class "Default")
      (node (ref "XB2") (pin "20") (pinfunction "AD0/DIO0_20") (pintype "bidirectional"))
    )
    (net (code "42") (name "XB_AD1") (class "Default")
      (node (ref "XB2") (pin "19") (pinfunction "AD1/DIO1_19") (pintype "bidirectional"))
    )
    (net (code "43") (name "XB_AD2") (class "Default")
      (node (ref "XB2") (pin "18") (pinfunction "AD2/DIO2_18") (pintype "bidirectional"))
    )
    (net (code "44") (name "XB_AD3") (class "Default")
      (node (ref "XB2") (pin "17") (pinfunction "COORD_SEL/AD3/DIO3_17") (pintype "bidirectional"))
    )
    (net (code "45") (name "XB_AD4") (class "Default")
      (node (ref "XB2") (pin "11") (pinfunction "RF_TX/AD4/DIO4_11") (pintype "bidirectional"))
    )
    (net (code "46") (name "XB_ASSOC") (class "Default")
      (node (ref "RN1") (pin "7") (pinfunction "2_7") (pintype "passive"))
      (node (ref "XB2") (pin "15") (pinfunction "ASSOC/AD5/DIO5_15") (pintype "bidirectional"))
    )
    (net (code "47") (name "XB_CTS") (class "Default")
      (node (ref "XB2") (pin "12") (pinfunction "~{CTS}/DIO7_12") (pintype "bidirectional"))
    )
    (net (code "48") (name "XB_DIN") (class "Default")
      (node (ref "IC9") (pin "4") (pinfunction "4_4") (pintype "bidirectional"))
      (node (ref "RN1") (pin "8") (pinfunction "2_8") (pintype "passive"))
      (node (ref "XB2") (pin "3") (pinfunction "DIN/~{CONFIG}_3") (pintype "input"))
    )
    (net (code "49") (name "XB_DIO12") (class "Default")
      (node (ref "XB2") (pin "4") (pinfunction "CD/DOUT_EN/DO8_4") (pintype "output"))
    )
    (net (code "50") (name "XB_DOUT") (class "Default")
      (node (ref "IC9") (pin "3") (pinfunction "3_3") (pintype "bidirectional"))
      (node (ref "RN2") (pin "8") (pinfunction "2_8") (pintype "passive"))
      (node (ref "XB2") (pin "2") (pinfunction "DOUT_2") (pintype "output"))
    )
    (net (code "51") (name "XB_DTR") (class "Default")
      (node (ref "XB2") (pin "9") (pinfunction "~{DTR}/SLEEP_RQ/DI8_9") (pintype "bidirectional"))
    )
    (net (code "52") (name "XB_RESET") (class "Default")
      (node (ref "XB2") (pin "5") (pinfunction "~{RESET}_5") (pintype "input"))
    )
    (net (code "53") (name "XB_RTS") (class "Default")
      (node (ref "XB2") (pin "16") (pinfunction "~{RTS}/AD6/DIO6_16") (pintype "bidirectional"))
    )
    (net (code "54") (name "XB_VREF") (class "Default")
      (node (ref "XB2") (pin "14") (pinfunction "VREF_14") (pintype "input"))
    )
    (net (code "55") (name "XIN") (class "Default")
      (node (ref "IC9") (pin "19") (pinfunction "19_19") (pintype "bidirectional"))
    )
    (net (code "56") (name "XOUT") (class "Default")
      (node (ref "IC9") (pin "18") (pinfunction "18_18") (pintype "bidirectional"))
    )
    (net (code "57") (name "_RST") (class "Default")
      (node (ref "C4") (pin "1") (pinfunction "1_1") (pintype "passive"))
      (node (ref "IC9") (pin "16") (pinfunction "16_16") (pintype "bidirectional"))
      (node (ref "JP2") (pin "3") (pinfunction "3_3") (pintype "passive"))
      (node (ref "JP3") (pin "3") (pinfunction "3_3") (pintype "passive"))
      (node (ref "R2") (pin "1") (pinfunction "1_1") (pintype "passive"))
      (node (ref "RESET") (pin "1") (pinfunction "1_1") (pintype "passive"))
      (node (ref "RESET") (pin "2") (pinfunction "2_2") (pintype "passive"))
    )
  )
)
